# sensor_sheild_smirf.net
KiCad netlist of a schematic drawn in EAGLE
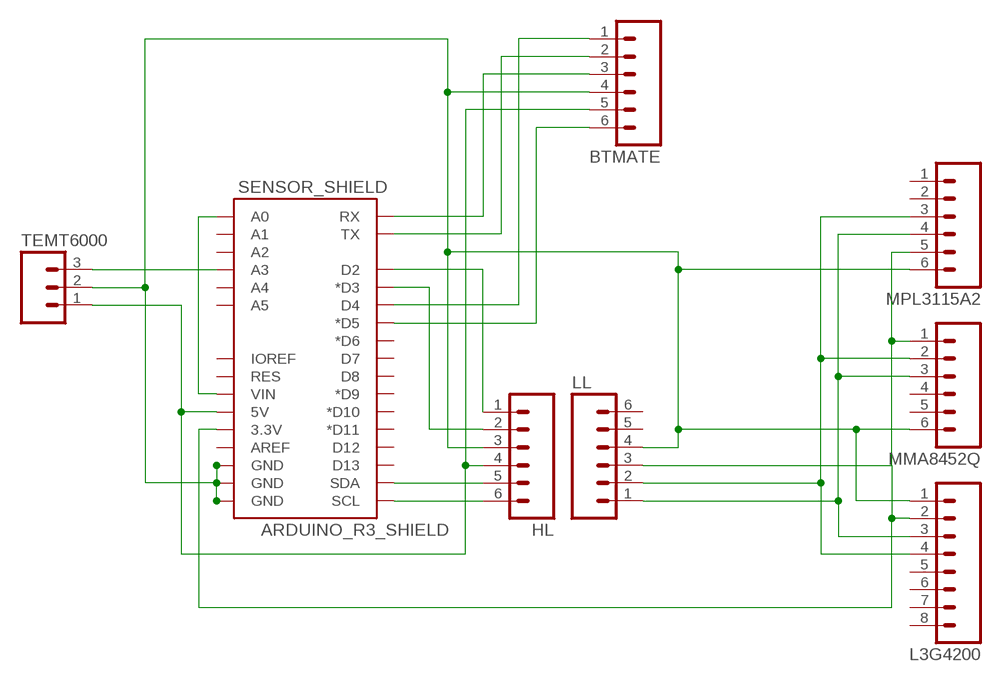
[diagram p0: schematic, sheet 1]

(export (version "E")
  (design (tool "Eeschema 10.0.6"))
  (components
    (comp (ref "BTMATE")
      (value "M06NO_SILK")
      (footprint "eagle-import:1X06_NO_SILK")
      (libsource (lib "eagle-import") (part "M06NO_SILK"))
    )
    (comp (ref "HL")
      (value "M06SIP")
      (footprint "eagle-import:1X06")
      (libsource (lib "eagle-import") (part "M06SIP"))
    )
    (comp (ref "L3G4200")
      (value "M08")
      (footprint "eagle-import:1X08_PIN1_NO_SILK")
      (libsource (lib "eagle-import") (part "M08"))
    )
    (comp (ref "LL")
      (value "M06SIP")
      (footprint "eagle-import:1X06")
      (libsource (lib "eagle-import") (part "M06SIP"))
    )
    (comp (ref "MMA8452Q")
      (value "M06SIP")
      (footprint "eagle-import:1X06")
      (libsource (lib "eagle-import") (part "M06SIP"))
    )
    (comp (ref "MPL3115A2")
      (value "M06SIP")
      (footprint "eagle-import:1X06")
      (libsource (lib "eagle-import") (part "M06SIP"))
    )
    (comp (ref "SENSOR_SHIELD")
      (value "ARDUINO_R3_SHIELD")
      (footprint "eagle-import:UNO_R3_SHIELD")
      (libsource (lib "eagle-import") (part "ARDUINO_R3_SHIELD"))
    )
    (comp (ref "TEMT6000")
      (value "M031X03_NO_SILK")
      (footprint "eagle-import:1X03_NO_SILK")
      (libsource (lib "eagle-import") (part "M031X03_NO_SILK"))
    )
  )
  (nets
    (net (code "1") (name "Net-(BTMATE-Pad1)") (class "Default")
      (node (ref "BTMATE") (pin "1") (pinfunction "1_1") (pintype "passive"))
      (node (ref "SENSOR_SHIELD") (pin "D4") (pinfunction "D4_D4") (pintype "bidirectional"))
    )
    (net (code "2") (name "Net-(BTMATE-Pad2)") (class "Default")
      (node (ref "BTMATE") (pin "2") (pinfunction "2_2") (pintype "passive"))
      (node (ref "SENSOR_SHIELD") (pin "TX") (pinfunction "TX_TX") (pintype "bidirectional"))
    )
    (net (code "3") (name "Net-(BTMATE-Pad3)") (class "Default")
      (node (ref "BTMATE") (pin "3") (pinfunction "3_3") (pintype "passive"))
      (node (ref "SENSOR_SHIELD") (pin "RX") (pinfunction "RX_RX") (pintype "bidirectional"))
    )
    (net (code "4") (name "Net-(BTMATE-Pad4)") (class "Default")
      (node (ref "BTMATE") (pin "4") (pinfunction "4_4") (pintype "passive"))
      (node (ref "HL") (pin "3") (pinfunction "3_3") (pintype "passive"))
      (node (ref "L3G4200") (pin "1") (pinfunction "1_1") (pintype "passive"))
      (node (ref "LL") (pin "4") (pinfunction "4_4") (pintype "passive"))
      (node (ref "MMA8452Q") (pin "6") (pinfunction "6_6") (pintype "passive"))
      (node (ref "MPL3115A2") (pin "6") (pinfunction "6_6") (pintype "passive"))
      (node (ref "SENSOR_SHIELD") (pin "GND@0") (pinfunction "GND_GND@0") (pintype "bidirectional"))
      (node (ref "SENSOR_SHIELD") (pin "GND@1") (pinfunction "GND_GND@1") (pintype "bidirectional"))
      (node (ref "SENSOR_SHIELD") (pin "GND@2") (pinfunction "GND_GND@2") (pintype "bidirectional"))
      (node (ref "TEMT6000") (pin "2") (pinfunction "2_2") (pintype "passive"))
    )
    (net (code "5") (name "Net-(BTMATE-Pad5)") (class "Default")
      (node (ref "BTMATE") (pin "5") (pinfunction "5_5") (pintype "passive"))
      (node (ref "HL") (pin "4") (pinfunction "4_4") (pintype "passive"))
      (node (ref "SENSOR_SHIELD") (pin "5V") (pinfunction "5V_5V") (pintype "bidirectional"))
      (node (ref "TEMT6000") (pin "1") (pinfunction "1_1") (pintype "passive"))
    )
    (net (code "6") (name "Net-(HL-Pad1)") (class "Default")
      (node (ref "HL") (pin "1") (pinfunction "1_1") (pintype "passive"))
      (node (ref "SENSOR_SHIELD") (pin "D2") (pinfunction "D2_D2") (pintype "bidirectional"))
    )
    (net (code "7") (name "Net-(HL-Pad5)") (class "Default")
      (node (ref "HL") (pin "5") (pinfunction "5_5") (pintype "passive"))
      (node (ref "SENSOR_SHIELD") (pin "SDA") (pinfunction "SDA_SDA") (pintype "bidirectional"))
    )
    (net (code "8") (name "Net-(HL-Pad6)") (class "Default")
      (node (ref "HL") (pin "6") (pinfunction "6_6") (pintype "passive"))
      (node (ref "SENSOR_SHIELD") (pin "SCL") (pinfunction "SCL_SCL") (pintype "bidirectional"))
    )
    (net (code "9") (name "Net-(L3G4200-Pad2)") (class "Default")
      (node (ref "L3G4200") (pin "2") (pinfunction "2_2") (pintype "passive"))
      (node (ref "LL") (pin "3") (pinfunction "3_3") (pintype "passive"))
      (node (ref "MMA8452Q") (pin "1") (pinfunction "1_1") (pintype "passive"))
      (node (ref "MPL3115A2") (pin "5") (pinfunction "5_5") (pintype "passive"))
      (node (ref "SENSOR_SHIELD") (pin "3.3V") (pinfunction "3.3V_3.3V") (pintype "bidirectional"))
    )
    (net (code "10") (name "Net-(L3G4200-Pad3)") (class "Default")
      (node (ref "L3G4200") (pin "3") (pinfunction "3_3") (pintype "passive"))
      (node (ref "LL") (pin "1") (pinfunction "1_1") (pintype "passive"))
      (node (ref "MMA8452Q") (pin "3") (pinfunction "3_3") (pintype "passive"))
      (node (ref "MPL3115A2") (pin "4") (pinfunction "4_4") (pintype "passive"))
    )
    (net (code "11") (name "Net-(L3G4200-Pad4)") (class "Default")
      (node (ref "L3G4200") (pin "4") (pinfunction "4_4") (pintype "passive"))
      (node (ref "LL") (pin "2") (pinfunction "2_2") (pintype "passive"))
      (node (ref "MMA8452Q") (pin "2") (pinfunction "2_2") (pintype "passive"))
      (node (ref "MPL3115A2") (pin "3") (pinfunction "3_3") (pintype "passive"))
    )
    (net (code "12") (name "Net-(SENSOR_SHIELD-*D3)") (class "Default")
      (node (ref "HL") (pin "2") (pinfunction "2_2") (pintype "passive"))
      (node (ref "SENSOR_SHIELD") (pin "D3") (pinfunction "*D3_D3") (pintype "bidirectional"))
    )
    (net (code "13") (name "Net-(SENSOR_SHIELD-*D5)") (class "Default")
      (node (ref "BTMATE") (pin "6") (pinfunction "6_6") (pintype "passive"))
      (node (ref "SENSOR_SHIELD") (pin "D5") (pinfunction "*D5_D5") (pintype "bidirectional"))
    )
    (net (code "14") (name "Net-(SENSOR_SHIELD-PadA0)") (class "Default")
      (node (ref "SENSOR_SHIELD") (pin "A0") (pinfunction "A0_A0") (pintype "bidirectional"))
      (node (ref "SENSOR_SHIELD") (pin "VIN") (pinfunction "VIN_VIN") (pintype "bidirectional"))
    )
    (net (code "15") (name "Net-(SENSOR_SHIELD-PadA3)") (class "Default")
      (node (ref "SENSOR_SHIELD") (pin "A3") (pinfunction "A3_A3") (pintype "bidirectional"))
      (node (ref "TEMT6000") (pin "3") (pinfunction "3_3") (pintype "passive"))
    )
    (net (code "16") (name "unconnected-(L3G4200-Pad5)") (class "Default")
      (node (ref "L3G4200") (pin "5") (pinfunction "5_5") (pintype "passive"))
    )
    (net (code "17") (name "unconnected-(L3G4200-Pad6)") (class "Default")
      (node (ref "L3G4200") (pin "6") (pinfunction "6_6") (pintype "passive"))
    )
    (net (code "18") (name "unconnected-(L3G4200-Pad7)") (class "Default")
      (node (ref "L3G4200") (pin "7") (pinfunction "7_7") (pintype "passive"))
    )
    (net (code "19") (name "unconnected-(L3G4200-Pad8)") (class "Default")
      (node (ref "L3G4200") (pin "8") (pinfunction "8_8") (pintype "passive"))
    )
    (net (code "20") (name "unconnected-(LL-Pad5)") (class "Default")
      (node (ref "LL") (pin "5") (pinfunction "5_5") (pintype "passive"))
    )
    (net (code "21") (name "unconnected-(LL-Pad6)") (class "Default")
      (node (ref "LL") (pin "6") (pinfunction "6_6") (pintype "passive"))
    )
    (net (code "22") (name "unconnected-(MMA8452Q-Pad4)") (class "Default")
      (node (ref "MMA8452Q") (pin "4") (pinfunction "4_4") (pintype "passive"))
    )
    (net (code "23") (name "unconnected-(MMA8452Q-Pad5)") (class "Default")
      (node (ref "MMA8452Q") (pin "5") (pinfunction "5_5") (pintype "passive"))
    )
    (net (code "24") (name "unconnected-(MPL3115A2-Pad1)") (class "Default")
      (node (ref "MPL3115A2") (pin "1") (pinfunction "1_1") (pintype "passive"))
    )
    (net (code "25") (name "unconnected-(MPL3115A2-Pad2)") (class "Default")
      (node (ref "MPL3115A2") (pin "2") (pinfunction "2_2") (pintype "passive"))
    )
    (net (code "26") (name "unconnected-(SENSOR_SHIELD-*D6-PadD6)") (class "Default")
      (node (ref "SENSOR_SHIELD") (pin "D6") (pinfunction "*D6_D6") (pintype "bidirectional"))
    )
    (net (code "27") (name "unconnected-(SENSOR_SHIELD-*D9-PadD9)") (class "Default")
      (node (ref "SENSOR_SHIELD") (pin "D9") (pinfunction "*D9_D9") (pintype "bidirectional"))
    )
    (net (code "28") (name "unconnected-(SENSOR_SHIELD-*D10-PadD10)") (class "Default")
      (node (ref "SENSOR_SHIELD") (pin "D10") (pinfunction "*D10_D10") (pintype "bidirectional"))
    )
    (net (code "29") (name "unconnected-(SENSOR_SHIELD-*D11-PadD11)") (class "Default")
      (node (ref "SENSOR_SHIELD") (pin "D11") (pinfunction "*D11_D11") (pintype "bidirectional"))
    )
    (net (code "30") (name "unconnected-(SENSOR_SHIELD-PadA1)") (class "Default")
      (node (ref "SENSOR_SHIELD") (pin "A1") (pinfunction "A1_A1") (pintype "bidirectional"))
    )
    (net (code "31") (name "unconnected-(SENSOR_SHIELD-PadA2)") (class "Default")
      (node (ref "SENSOR_SHIELD") (pin "A2") (pinfunction "A2_A2") (pintype "bidirectional"))
    )
    (net (code "32") (name "unconnected-(SENSOR_SHIELD-PadA4)") (class "Default")
      (node (ref "SENSOR_SHIELD") (pin "A4") (pinfunction "A4_A4") (pintype "bidirectional"))
    )
    (net (code "33") (name "unconnected-(SENSOR_SHIELD-PadA5)") (class "Default")
      (node (ref "SENSOR_SHIELD") (pin "A5") (pinfunction "A5_A5") (pintype "bidirectional"))
    )
    (net (code "34") (name "unconnected-(SENSOR_SHIELD-PadAREF)") (class "Default")
      (node (ref "SENSOR_SHIELD") (pin "AREF") (pinfunction "AREF_AREF") (pintype "bidirectional"))
    )
    (net (code "35") (name "unconnected-(SENSOR_SHIELD-PadD7)") (class "Default")
      (node (ref "SENSOR_SHIELD") (pin "D7") (pinfunction "D7_D7") (pintype "bidirectional"))
    )
    (net (code "36") (name "unconnected-(SENSOR_SHIELD-PadD8)") (class "Default")
      (node (ref "SENSOR_SHIELD") (pin "D8") (pinfunction "D8_D8") (pintype "bidirectional"))
    )
    (net (code "37") (name "unconnected-(SENSOR_SHIELD-PadD12)") (class "Default")
      (node (ref "SENSOR_SHIELD") (pin "D12") (pinfunction "D12_D12") (pintype "bidirectional"))
    )
    (net (code "38") (name "unconnected-(SENSOR_SHIELD-PadD13)") (class "Default")
      (node (ref "SENSOR_SHIELD") (pin "D13") (pinfunction "D13_D13") (pintype "bidirectional"))
    )
    (net (code "39") (name "unconnected-(SENSOR_SHIELD-PadIOREF)") (class "Default")
      (node (ref "SENSOR_SHIELD") (pin "IOREF") (pinfunction "IOREF_IOREF") (pintype "bidirectional"))
    )
    (net (code "40") (name "unconnected-(SENSOR_SHIELD-PadRES)") (class "Default")
      (node (ref "SENSOR_SHIELD") (pin "RES") (pinfunction "RES_RES") (pintype "bidirectional"))
    )
  )
)
